# current_amplification.net
KiCad netlist of a schematic drawn in Altium Designer
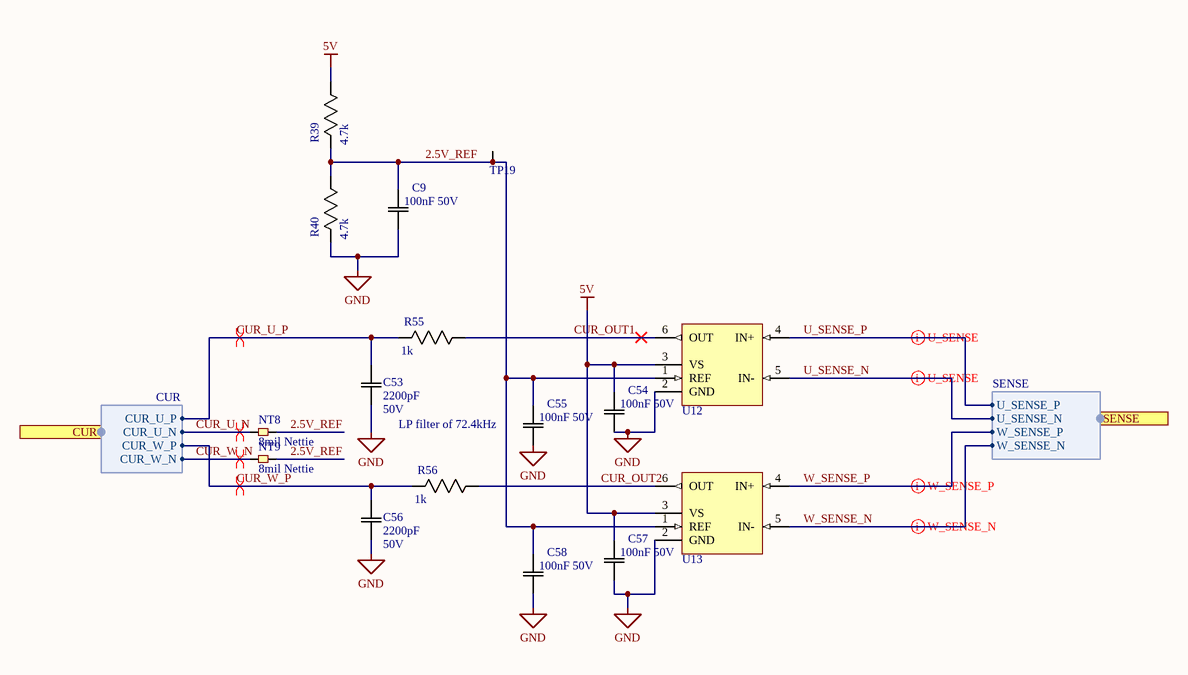
[diagram p0: current_amplification.SchDoc]

(export (version "E")
  (design (tool "Eeschema 10.0.6"))
  (components
    (comp (ref "C9")
      (value "100nF 50V")
      (footprint "0603")
      (description "Default Symbol for Capacitors")
      (fields (field (name "TOLERANCE") "10%") (field (name "PART NUMBER") "CAP 100nF 50V"))
      (libsource (lib "capacitor_library") (part "CAP_Default"))
    )
    (comp (ref "C53")
      (value "2200pF")
      (footprint "0603")
      (description "Default Symbol for Capacitors")
      (fields
        (field (name "TOLERANCE") "10%")
        (field (name "RATING") "50V")
        (field (name "PART NUMBER") "CAP 2200pF 50V")
      )
      (libsource (lib "capacitor_library") (part "CAP_Default"))
    )
    (comp (ref "C54")
      (value "100nF 50V")
      (footprint "0603")
      (description "Default Symbol for Capacitors")
      (fields (field (name "TOLERANCE") "10%") (field (name "PART NUMBER") "CAP 100nF 50V"))
      (libsource (lib "capacitor_library") (part "CAP_Default"))
    )
    (comp (ref "C55")
      (value "100nF 50V")
      (footprint "0603")
      (description "Default Symbol for Capacitors")
      (fields (field (name "TOLERANCE") "10%") (field (name "PART NUMBER") "CAP 100nF 50V"))
      (libsource (lib "capacitor_library") (part "CAP_Default"))
    )
    (comp (ref "C56")
      (value "2200pF")
      (footprint "0603")
      (description "Default Symbol for Capacitors")
      (fields
        (field (name "TOLERANCE") "10%")
        (field (name "RATING") "50V")
        (field (name "PART NUMBER") "CAP 2200pF 50V")
      )
      (libsource (lib "capacitor_library") (part "CAP_Default"))
    )
    (comp (ref "C57")
      (value "100nF 50V")
      (footprint "0603")
      (description "Default Symbol for Capacitors")
      (fields (field (name "TOLERANCE") "10%") (field (name "PART NUMBER") "CAP 100nF 50V"))
      (libsource (lib "capacitor_library") (part "CAP_Default"))
    )
    (comp (ref "C58")
      (value "100nF 50V")
      (footprint "0603")
      (description "Default Symbol for Capacitors")
      (fields (field (name "TOLERANCE") "10%") (field (name "PART NUMBER") "CAP 100nF 50V"))
      (libsource (lib "capacitor_library") (part "CAP_Default"))
    )
    (comp (ref "NT8")
      (value "8mil Nettie")
      (footprint "NT_8mil")
      (description "8mil wide nettie")
      (fields (field (name "PART NUMBER") "NT_8"))
      (libsource (lib "IC_Library") (part "NT_8"))
    )
    (comp (ref "NT9")
      (value "8mil Nettie")
      (footprint "NT_8mil")
      (description "8mil wide nettie")
      (fields (field (name "PART NUMBER") "NT_8"))
      (libsource (lib "IC_Library") (part "NT_8"))
    )
    (comp (ref "R39")
      (value "4.7k")
      (footprint "0603")
      (description "Default Resistor Symbol")
      (fields (field (name "TOLERANCE") "1%") (field (name "PART NUMBER") "RES 4.7k 1/8W - 1%"))
      (libsource (lib "Resistor_Library") (part "RES_DEFAULT"))
    )
    (comp (ref "R40")
      (value "4.7k")
      (footprint "0603")
      (description "Default Resistor Symbol")
      (fields (field (name "TOLERANCE") "1%") (field (name "PART NUMBER") "RES 4.7k 1/8W - 1%"))
      (libsource (lib "") (part "RES_DEFAULT_1"))
    )
    (comp (ref "R55")
      (value "1k")
      (footprint "0603")
      (description "Default Resistor Symbol")
      (fields (field (name "TOLERANCE") "1%") (field (name "PART NUMBER") "RES 1k 1/8W - 1%"))
      (libsource (lib "Resistor_Library") (part "RES_DEFAULT"))
    )
    (comp (ref "R56")
      (value "1k")
      (footprint "0603")
      (description "Default Resistor Symbol")
      (fields (field (name "TOLERANCE") "1%") (field (name "PART NUMBER") "RES 1k 1/8W - 1%"))
      (libsource (lib "Resistor_Library") (part "RES_DEFAULT"))
    )
    (comp (ref "TP19")
      (value "Test Point (Via)")
      (footprint "TP")
      (libsource (lib "IC_Library") (part "Test Point (Via)"))
    )
    (comp (ref "U12")
      (value "OP AMP CURR SENSE BI TSC")
      (footprint "SC70-6")
      (description "SP Amp Current Sense Amp Single R-R O/P 5.5V Automotive 6-Pin SC-70 T/R")
      (libsource (lib "IC_Library") (part "OP AMP CURR SENSE BI TSC"))
    )
    (comp (ref "U13")
      (value "OP AMP CURR SENSE BI TSC")
      (footprint "SC70-6")
      (description "SP Amp Current Sense Amp Single R-R O/P 5.5V Automotive 6-Pin SC-70 T/R")
      (libsource (lib "IC_Library") (part "OP AMP CURR SENSE BI TSC"))
    )
  )
  (nets
    (net (code "3") (name "/2.5V_REF") (class "Default")
      (node (ref "C55") (pin "2") (pinfunction "C2_2") (pintype "passive"))
      (node (ref "C58") (pin "2") (pinfunction "C2_2") (pintype "passive"))
      (node (ref "C9") (pin "2") (pinfunction "C2_2") (pintype "passive"))
      (node (ref "NT8") (pin "2") (pinfunction "2_2") (pintype "passive"))
      (node (ref "NT9") (pin "2") (pinfunction "2_2") (pintype "passive"))
      (node (ref "R39") (pin "2") (pinfunction "R2_2") (pintype "passive"))
      (node (ref "R40") (pin "1") (pinfunction "R1_1") (pintype "passive"))
      (node (ref "TP19") (pin "1") (pinfunction "1_1") (pintype "passive"))
      (node (ref "U12") (pin "1") (pinfunction "REF_1") (pintype "input"))
      (node (ref "U13") (pin "1") (pinfunction "REF_1") (pintype "input"))
    )
    (net (code "4") (name "/CUR_OUT1") (class "Default")
      (node (ref "R55") (pin "1") (pinfunction "R1_1") (pintype "passive"))
      (node (ref "U12") (pin "6") (pinfunction "OUT_6") (pintype "output"))
    )
    (net (code "5") (name "/CUR_OUT2") (class "Default")
      (node (ref "R56") (pin "1") (pinfunction "R1_1") (pintype "passive"))
      (node (ref "U13") (pin "6") (pinfunction "OUT_6") (pintype "output"))
    )
    (net (code "6") (name "/CUR_U_N") (class "Default")
      (node (ref "NT8") (pin "1") (pinfunction "1_1") (pintype "passive"))
    )
    (net (code "7") (name "/CUR_U_P") (class "Default")
      (node (ref "C53") (pin "2") (pinfunction "C2_2") (pintype "passive"))
      (node (ref "R55") (pin "2") (pinfunction "R2_2") (pintype "passive"))
    )
    (net (code "8") (name "/CUR_W_N") (class "Default")
      (node (ref "NT9") (pin "1") (pinfunction "1_1") (pintype "passive"))
    )
    (net (code "9") (name "/CUR_W_P") (class "Default")
      (node (ref "C56") (pin "2") (pinfunction "C2_2") (pintype "passive"))
      (node (ref "R56") (pin "2") (pinfunction "R2_2") (pintype "passive"))
    )
    (net (code "10") (name "/U_SENSE_N") (class "Default")
      (node (ref "U12") (pin "5") (pinfunction "IN-_5") (pintype "input"))
    )
    (net (code "11") (name "/U_SENSE_P") (class "Default")
      (node (ref "U12") (pin "4") (pinfunction "IN+_4") (pintype "input"))
    )
    (net (code "12") (name "/W_SENSE_N") (class "Default")
      (node (ref "U13") (pin "5") (pinfunction "IN-_5") (pintype "input"))
    )
    (net (code "13") (name "/W_SENSE_P") (class "Default")
      (node (ref "U13") (pin "4") (pinfunction "IN+_4") (pintype "input"))
    )
    (net (code "16") (name "5V") (class "Default")
      (node (ref "C54") (pin "2") (pinfunction "C2_2") (pintype "passive"))
      (node (ref "C57") (pin "2") (pinfunction "C2_2") (pintype "passive"))
      (node (ref "R39") (pin "1") (pinfunction "R1_1") (pintype "passive"))
      (node (ref "U12") (pin "3") (pinfunction "VS_3") (pintype "power_in"))
      (node (ref "U13") (pin "3") (pinfunction "VS_3") (pintype "power_in"))
    )
    (net (code "17") (name "GND") (class "Default")
      (node (ref "C53") (pin "1") (pinfunction "C1_1") (pintype "passive"))
      (node (ref "C54") (pin "1") (pinfunction "C1_1") (pintype "passive"))
      (node (ref "C55") (pin "1") (pinfunction "C1_1") (pintype "passive"))
      (node (ref "C56") (pin "1") (pinfunction "C1_1") (pintype "passive"))
      (node (ref "C57") (pin "1") (pinfunction "C1_1") (pintype "passive"))
      (node (ref "C58") (pin "1") (pinfunction "C1_1") (pintype "passive"))
      (node (ref "C9") (pin "1") (pinfunction "C1_1") (pintype "passive"))
      (node (ref "R40") (pin "2") (pinfunction "R2_2") (pintype "passive"))
      (node (ref "U12") (pin "2") (pinfunction "GND_2") (pintype "power_in"))
      (node (ref "U13") (pin "2") (pinfunction "GND_2") (pintype "power_in"))
    )
  )
)
